# vca.net
KiCad netlist of a schematic drawn in Altium Designer
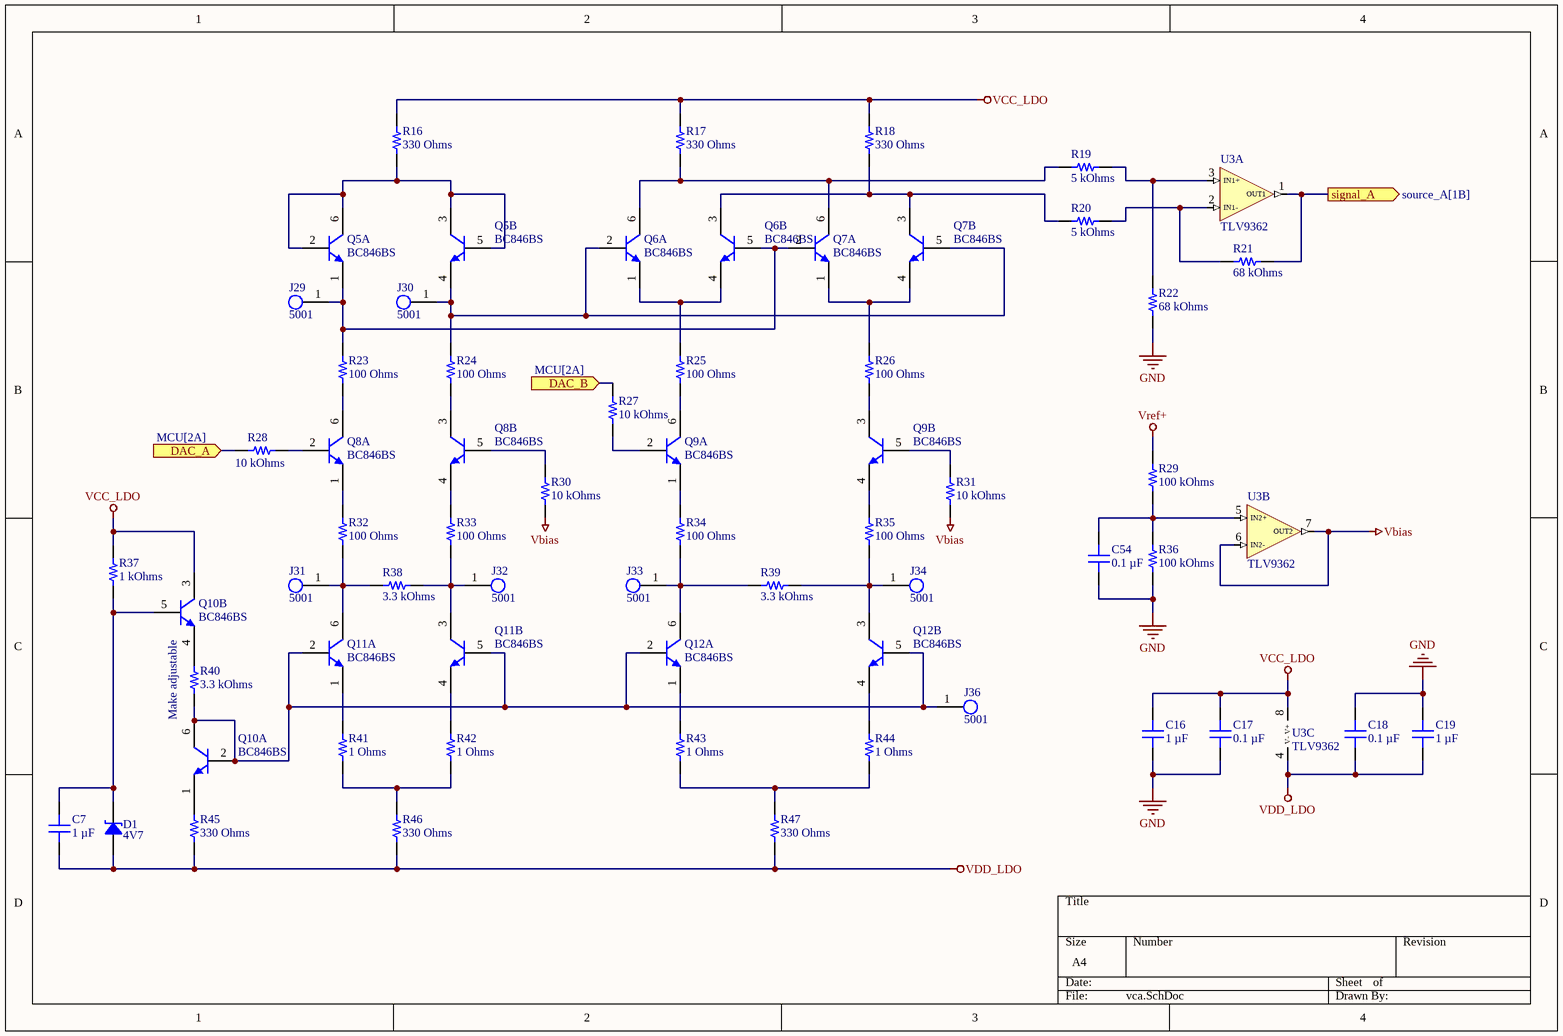
[diagram p0: vca.SchDoc]

(export (version "E")
  (design (tool "Eeschema 10.0.6"))
  (components
    (comp (ref "C7")
      (value "1 µF")
      (footprint "CAP 1206_3216 - 0.8MM")
      (description "CAP CER 1UF 50V X7R 1206")
      (fields
        (field (name "PART NUMBER") "885012208093")
        (field (name "CAPACITANCE") "1 µF")
        (field (name "MANUFACTURER") "Würth Elektronik")
      )
      (libsource (lib "Celestial Altium Library - altium_library") (part "Capacitor"))
    )
    (comp (ref "C16")
      (value "1 µF")
      (footprint "CAP 1206_3216 - 0.8MM")
      (description "CAP CER 1UF 50V X7R 1206")
      (fields
        (field (name "PART NUMBER") "885012208093")
        (field (name "CAPACITANCE") "1 µF")
        (field (name "MANUFACTURER") "Würth Elektronik")
      )
      (libsource (lib "Celestial Altium Library - altium_library") (part "Capacitor"))
    )
    (comp (ref "C17")
      (value "0.1 µF")
      (footprint "CAP 1206_3216 - 0.8MM")
      (description "CAP CER 0.1UF 50V X7R 1206")
      (fields
        (field (name "PART NUMBER") "885012208087")
        (field (name "CAPACITANCE") "0.1 µF")
        (field (name "MANUFACTURER") "Würth Elektronik")
      )
      (libsource (lib "Celestial Altium Library - altium_library") (part "Capacitor"))
    )
    (comp (ref "C18")
      (value "0.1 µF")
      (footprint "CAP 1206_3216 - 0.8MM")
      (description "CAP CER 0.1UF 50V X7R 1206")
      (fields
        (field (name "PART NUMBER") "885012208087")
        (field (name "CAPACITANCE") "0.1 µF")
        (field (name "MANUFACTURER") "Würth Elektronik")
      )
      (libsource (lib "Celestial Altium Library - altium_library") (part "Capacitor"))
    )
    (comp (ref "C19")
      (value "1 µF")
      (footprint "CAP 1206_3216 - 0.8MM")
      (description "CAP CER 1UF 50V X7R 1206")
      (fields
        (field (name "PART NUMBER") "885012208093")
        (field (name "CAPACITANCE") "1 µF")
        (field (name "MANUFACTURER") "Würth Elektronik")
      )
      (libsource (lib "Celestial Altium Library - altium_library") (part "Capacitor"))
    )
    (comp (ref "C54")
      (value "0.1 µF")
      (footprint "CAP 1206_3216 - 0.8MM")
      (description "CAP CER 0.1UF 50V X7R 1206")
      (fields
        (field (name "PART NUMBER") "885012208087")
        (field (name "CAPACITANCE") "0.1 µF")
        (field (name "MANUFACTURER") "Würth Elektronik")
      )
      (libsource (lib "Celestial Altium Library - altium_library") (part "Capacitor"))
    )
    (comp (ref "D1") (value "4V7") (footprint "SOD323") (libsource (lib "za_koncar") (part "BZX38450-C4V7X")))
    (comp (ref "J29")
      (value "5001")
      (footprint "FP-5001-MFG")
      (description "PC TEST POINT MINIATURE BLACK")
      (libsource (lib "za_koncar") (part "CMP-2000-05181-2"))
    )
    (comp (ref "J30")
      (value "5001")
      (footprint "FP-5001-MFG")
      (description "PC TEST POINT MINIATURE BLACK")
      (libsource (lib "za_koncar") (part "CMP-2000-05181-2"))
    )
    (comp (ref "J31")
      (value "5001")
      (footprint "FP-5001-MFG")
      (description "PC TEST POINT MINIATURE BLACK")
      (libsource (lib "za_koncar") (part "CMP-2000-05181-2"))
    )
    (comp (ref "J32")
      (value "5001")
      (footprint "FP-5001-MFG")
      (description "PC TEST POINT MINIATURE BLACK")
      (libsource (lib "za_koncar") (part "CMP-2000-05181-2"))
    )
    (comp (ref "J33")
      (value "5001")
      (footprint "FP-5001-MFG")
      (description "PC TEST POINT MINIATURE BLACK")
      (libsource (lib "za_koncar") (part "CMP-2000-05181-2"))
    )
    (comp (ref "J34")
      (value "5001")
      (footprint "FP-5001-MFG")
      (description "PC TEST POINT MINIATURE BLACK")
      (libsource (lib "za_koncar") (part "CMP-2000-05181-2"))
    )
    (comp (ref "J36")
      (value "5001")
      (footprint "FP-5001-MFG")
      (description "PC TEST POINT MINIATURE BLACK")
      (libsource (lib "za_koncar") (part "CMP-2000-05181-2"))
    )
    (comp (ref "Q5")
      (value "BC846BS")
      (footprint "TSOP65P210X110-6N")
      (description "65 V, 100 mA matched NPN/NPN general-purpose transistor")
      (libsource (lib "za_koncar") (part "BC846BS"))
    )
    (comp (ref "Q6")
      (value "BC846BS")
      (footprint "TSOP65P210X110-6N")
      (description "65 V, 100 mA matched NPN/NPN general-purpose transistor")
      (libsource (lib "za_koncar") (part "BC846BS"))
    )
    (comp (ref "Q7")
      (value "BC846BS")
      (footprint "TSOP65P210X110-6N")
      (description "65 V, 100 mA matched NPN/NPN general-purpose transistor")
      (libsource (lib "za_koncar") (part "BC846BS"))
    )
    (comp (ref "Q8")
      (value "BC846BS")
      (footprint "TSOP65P210X110-6N")
      (description "65 V, 100 mA matched NPN/NPN general-purpose transistor")
      (libsource (lib "za_koncar") (part "BC846BS"))
    )
    (comp (ref "Q9")
      (value "BC846BS")
      (footprint "TSOP65P210X110-6N")
      (description "65 V, 100 mA matched NPN/NPN general-purpose transistor")
      (libsource (lib "za_koncar") (part "BC846BS"))
    )
    (comp (ref "Q10")
      (value "BC846BS")
      (footprint "TSOP65P210X110-6N")
      (description "65 V, 100 mA matched NPN/NPN general-purpose transistor")
      (libsource (lib "za_koncar") (part "BC846BS"))
    )
    (comp (ref "Q11")
      (value "BC846BS")
      (footprint "TSOP65P210X110-6N")
      (description "65 V, 100 mA matched NPN/NPN general-purpose transistor")
      (libsource (lib "za_koncar") (part "BC846BS"))
    )
    (comp (ref "Q12")
      (value "BC846BS")
      (footprint "TSOP65P210X110-6N")
      (description "65 V, 100 mA matched NPN/NPN general-purpose transistor")
      (libsource (lib "za_koncar") (part "BC846BS"))
    )
    (comp (ref "R16")
      (value "330 Ohms")
      (footprint "YAGEO RES 1206_3216")
      (description "RES SMD 330 OHM 1% 1/4W 1206")
      (fields (field (name "PART NUMBER") "RT1206FRD07330RL") (field (name "MANUFACTURER") "Yageo"))
      (libsource (lib "Celestial Altium Library - altium_library") (part "Resistor"))
    )
    (comp (ref "R17")
      (value "330 Ohms")
      (footprint "YAGEO RES 1206_3216")
      (description "RES SMD 330 OHM 1% 1/4W 1206")
      (fields (field (name "PART NUMBER") "RT1206FRD07330RL") (field (name "MANUFACTURER") "Yageo"))
      (libsource (lib "Celestial Altium Library - altium_library") (part "Resistor"))
    )
    (comp (ref "R18")
      (value "330 Ohms")
      (footprint "YAGEO RES 1206_3216")
      (description "RES SMD 330 OHM 1% 1/4W 1206")
      (fields (field (name "PART NUMBER") "RT1206FRD07330RL") (field (name "MANUFACTURER") "Yageo"))
      (libsource (lib "Celestial Altium Library - altium_library") (part "Resistor"))
    )
    (comp (ref "R19")
      (value "5 kOhms")
      (footprint "YAGEO RES 1206_3216")
      (description "RES 5K OHM 1% 1/4W 1206")
      (fields (field (name "PART NUMBER") "RT1206FRE075KL") (field (name "MANUFACTURER") "Yageo"))
      (libsource (lib "Celestial Altium Library - altium_library") (part "Resistor"))
    )
    (comp (ref "R20")
      (value "5 kOhms")
      (footprint "YAGEO RES 1206_3216")
      (description "RES 5K OHM 1% 1/4W 1206")
      (fields (field (name "PART NUMBER") "RT1206FRE075KL") (field (name "MANUFACTURER") "Yageo"))
      (libsource (lib "Celestial Altium Library - altium_library") (part "Resistor"))
    )
    (comp (ref "R21")
      (value "68 kOhms")
      (footprint "YAGEO RES 1206_3216")
      (description "RES SMD 68K OHM 1% 1/4W 1206")
      (fields (field (name "PART NUMBER") "RT1206FRE0768KL") (field (name "MANUFACTURER") "Yageo"))
      (libsource (lib "Celestial Altium Library - altium_library") (part "Resistor"))
    )
    (comp (ref "R22")
      (value "68 kOhms")
      (footprint "YAGEO RES 1206_3216")
      (description "RES SMD 68K OHM 1% 1/4W 1206")
      (fields (field (name "PART NUMBER") "RT1206FRE0768KL") (field (name "MANUFACTURER") "Yageo"))
      (libsource (lib "Celestial Altium Library - altium_library") (part "Resistor"))
    )
    (comp (ref "R23")
      (value "100 Ohms")
      (footprint "YAGEO RES 1206_3216")
      (description "RES SMD 100 OHM 1% 1/4W 1206")
      (fields (field (name "PART NUMBER") "RT1206FRD07100RL") (field (name "MANUFACTURER") "Yageo"))
      (libsource (lib "Celestial Altium Library - altium_library") (part "Resistor"))
    )
    (comp (ref "R24")
      (value "100 Ohms")
      (footprint "YAGEO RES 1206_3216")
      (description "RES SMD 100 OHM 1% 1/4W 1206")
      (fields (field (name "PART NUMBER") "RT1206FRD07100RL") (field (name "MANUFACTURER") "Yageo"))
      (libsource (lib "Celestial Altium Library - altium_library") (part "Resistor"))
    )
    (comp (ref "R25")
      (value "100 Ohms")
      (footprint "YAGEO RES 1206_3216")
      (description "RES SMD 100 OHM 1% 1/4W 1206")
      (fields (field (name "PART NUMBER") "RT1206FRD07100RL") (field (name "MANUFACTURER") "Yageo"))
      (libsource (lib "Celestial Altium Library - altium_library") (part "Resistor"))
    )
    (comp (ref "R26")
      (value "100 Ohms")
      (footprint "YAGEO RES 1206_3216")
      (description "RES SMD 100 OHM 1% 1/4W 1206")
      (fields (field (name "PART NUMBER") "RT1206FRD07100RL") (field (name "MANUFACTURER") "Yageo"))
      (libsource (lib "Celestial Altium Library - altium_library") (part "Resistor"))
    )
    (comp (ref "R27")
      (value "10 kOhms")
      (footprint "YAGEO RES 1206_3216")
      (description "RES SMD 10K OHM 1% 1/4W 1206")
      (fields (field (name "PART NUMBER") "RT1206FRE0710KL") (field (name "MANUFACTURER") "Yageo"))
      (libsource (lib "Celestial Altium Library - altium_library") (part "Resistor"))
    )
    (comp (ref "R28")
      (value "10 kOhms")
      (footprint "YAGEO RES 1206_3216")
      (description "RES SMD 10K OHM 1% 1/4W 1206")
      (fields (field (name "PART NUMBER") "RT1206FRE0710KL") (field (name "MANUFACTURER") "Yageo"))
      (libsource (lib "Celestial Altium Library - altium_library") (part "Resistor"))
    )
    (comp (ref "R29")
      (value "100 kOhms")
      (footprint "YAGEO RES 1206_3216")
      (description "RES SMD 100K OHM 1% 1/4W 1206")
      (fields (field (name "PART NUMBER") "RT1206FRE07100KL") (field (name "MANUFACTURER") "Yageo"))
      (libsource (lib "Celestial Altium Library - altium_library") (part "Resistor"))
    )
    (comp (ref "R30")
      (value "10 kOhms")
      (footprint "YAGEO RES 1206_3216")
      (description "RES SMD 10K OHM 1% 1/4W 1206")
      (fields (field (name "PART NUMBER") "RT1206FRE0710KL") (field (name "MANUFACTURER") "Yageo"))
      (libsource (lib "Celestial Altium Library - altium_library") (part "Resistor"))
    )
    (comp (ref "R31")
      (value "10 kOhms")
      (footprint "YAGEO RES 1206_3216")
      (description "RES SMD 10K OHM 1% 1/4W 1206")
      (fields (field (name "PART NUMBER") "RT1206FRE0710KL") (field (name "MANUFACTURER") "Yageo"))
      (libsource (lib "Celestial Altium Library - altium_library") (part "Resistor"))
    )
    (comp (ref "R32")
      (value "100 Ohms")
      (footprint "YAGEO RES 1206_3216")
      (description "RES SMD 100 OHM 1% 1/4W 1206")
      (fields (field (name "PART NUMBER") "RT1206FRD07100RL") (field (name "MANUFACTURER") "Yageo"))
      (libsource (lib "Celestial Altium Library - altium_library") (part "Resistor"))
    )
    (comp (ref "R33")
      (value "100 Ohms")
      (footprint "YAGEO RES 1206_3216")
      (description "RES SMD 100 OHM 1% 1/4W 1206")
      (fields (field (name "PART NUMBER") "RT1206FRD07100RL") (field (name "MANUFACTURER") "Yageo"))
      (libsource (lib "Celestial Altium Library - altium_library") (part "Resistor"))
    )
    (comp (ref "R34")
      (value "100 Ohms")
      (footprint "YAGEO RES 1206_3216")
      (description "RES SMD 100 OHM 1% 1/4W 1206")
      (fields (field (name "PART NUMBER") "RT1206FRD07100RL") (field (name "MANUFACTURER") "Yageo"))
      (libsource (lib "Celestial Altium Library - altium_library") (part "Resistor"))
    )
    (comp (ref "R35")
      (value "100 Ohms")
      (footprint "YAGEO RES 1206_3216")
      (description "RES SMD 100 OHM 1% 1/4W 1206")
      (fields (field (name "PART NUMBER") "RT1206FRD07100RL") (field (name "MANUFACTURER") "Yageo"))
      (libsource (lib "Celestial Altium Library - altium_library") (part "Resistor"))
    )
    (comp (ref "R36")
      (value "100 kOhms")
      (footprint "YAGEO RES 1206_3216")
      (description "RES SMD 100K OHM 1% 1/4W 1206")
      (fields (field (name "PART NUMBER") "RT1206FRE07100KL") (field (name "MANUFACTURER") "Yageo"))
      (libsource (lib "Celestial Altium Library - altium_library") (part "Resistor"))
    )
    (comp (ref "R37")
      (value "1 kOhms")
      (footprint "YAGEO RES 1206_3216")
      (description "RES SMD 1K OHM 1% 1/4W 1206")
      (fields (field (name "PART NUMBER") "RT1206FRE071KL") (field (name "MANUFACTURER") "Yageo"))
      (libsource (lib "Celestial Altium Library - altium_library") (part "Resistor"))
    )
    (comp (ref "R38")
      (value "3.3 kOhms")
      (footprint "YAGEO RES 1206_3216")
      (description "RES SMD 3.3K OHM 1% 1/4W 1206")
      (fields (field (name "PART NUMBER") "RT1206FRE073K3L") (field (name "MANUFACTURER") "Yageo"))
      (libsource (lib "Celestial Altium Library - altium_library") (part "Resistor"))
    )
    (comp (ref "R39")
      (value "3.3 kOhms")
      (footprint "YAGEO RES 1206_3216")
      (description "RES SMD 3.3K OHM 1% 1/4W 1206")
      (fields (field (name "PART NUMBER") "RT1206FRE073K3L") (field (name "MANUFACTURER") "Yageo"))
      (libsource (lib "Celestial Altium Library - altium_library") (part "Resistor"))
    )
    (comp (ref "R40")
      (value "3.3 kOhms")
      (footprint "YAGEO RES 1206_3216")
      (description "RES SMD 3.3K OHM 1% 1/4W 1206")
      (fields (field (name "PART NUMBER") "RT1206FRE073K3L") (field (name "MANUFACTURER") "Yageo"))
      (libsource (lib "Celestial Altium Library - altium_library") (part "Resistor"))
    )
    (comp (ref "R41")
      (value "1 Ohms")
      (footprint "YAGEO RES 1206_3216")
      (description "RES 1 OHM 0.1% 1/4W 1206")
      (fields (field (name "PART NUMBER") "RT1206BRD071RL") (field (name "MANUFACTURER") "Yageo"))
      (libsource (lib "Celestial Altium Library - altium_library") (part "Resistor"))
    )
    (comp (ref "R42")
      (value "1 Ohms")
      (footprint "YAGEO RES 1206_3216")
      (description "RES 1 OHM 0.1% 1/4W 1206")
      (fields (field (name "PART NUMBER") "RT1206BRD071RL") (field (name "MANUFACTURER") "Yageo"))
      (libsource (lib "Celestial Altium Library - altium_library") (part "Resistor"))
    )
    (comp (ref "R43")
      (value "1 Ohms")
      (footprint "YAGEO RES 1206_3216")
      (description "RES 1 OHM 0.1% 1/4W 1206")
      (fields (field (name "PART NUMBER") "RT1206BRD071RL") (field (name "MANUFACTURER") "Yageo"))
      (libsource (lib "Celestial Altium Library - altium_library") (part "Resistor"))
    )
    (comp (ref "R44")
      (value "1 Ohms")
      (footprint "YAGEO RES 1206_3216")
      (description "RES 1 OHM 0.1% 1/4W 1206")
      (fields (field (name "PART NUMBER") "RT1206BRD071RL") (field (name "MANUFACTURER") "Yageo"))
      (libsource (lib "Celestial Altium Library - altium_library") (part "Resistor"))
    )
    (comp (ref "R45")
      (value "330 Ohms")
      (footprint "YAGEO RES 1206_3216")
      (description "RES SMD 330 OHM 1% 1/4W 1206")
      (fields (field (name "PART NUMBER") "RT1206FRD07330RL") (field (name "MANUFACTURER") "Yageo"))
      (libsource (lib "Celestial Altium Library - altium_library") (part "Resistor"))
    )
    (comp (ref "R46")
      (value "330 Ohms")
      (footprint "YAGEO RES 1206_3216")
      (description "RES SMD 330 OHM 1% 1/4W 1206")
      (fields (field (name "PART NUMBER") "RT1206FRD07330RL") (field (name "MANUFACTURER") "Yageo"))
      (libsource (lib "Celestial Altium Library - altium_library") (part "Resistor"))
    )
    (comp (ref "R47")
      (value "330 Ohms")
      (footprint "YAGEO RES 1206_3216")
      (description "RES SMD 330 OHM 1% 1/4W 1206")
      (fields (field (name "PART NUMBER") "RT1206FRD07330RL") (field (name "MANUFACTURER") "Yageo"))
      (libsource (lib "Celestial Altium Library - altium_library") (part "Resistor"))
    )
    (comp (ref "U3")
      (value "TLV9362")
      (footprint "za_koncar:SOIC8-127P600X175-8N")
      (description "TLV936x 10-MHz, 40-V, RRO, Operational Amplifie")
      (libsource (lib "za_koncar") (part "TLV9362"))
    )
  )
  (nets
    (net (code "1") (name "/DAC_A") (class "Default")
      (node (ref "R28") (pin "1") (pinfunction "1_1") (pintype "passive"))
    )
    (net (code "2") (name "/DAC_B") (class "Default")
      (node (ref "R27") (pin "1") (pinfunction "1_1") (pintype "passive"))
    )
    (net (code "3") (name "/signal_A") (class "Default")
      (node (ref "R21") (pin "1") (pinfunction "1_1") (pintype "passive"))
      (node (ref "U3") (pin "1") (pinfunction "OUT1_1") (pintype "output"))
    )
    (net (code "4") (name "GND") (class "Default")
      (node (ref "C16") (pin "1") (pinfunction "1_1") (pintype "passive"))
      (node (ref "C17") (pin "1") (pinfunction "1_1") (pintype "passive"))
      (node (ref "C18") (pin "2") (pinfunction "2_2") (pintype "passive"))
      (node (ref "C19") (pin "2") (pinfunction "2_2") (pintype "passive"))
      (node (ref "C54") (pin "1") (pinfunction "1_1") (pintype "passive"))
      (node (ref "R22") (pin "2") (pinfunction "2_2") (pintype "passive"))
      (node (ref "R36") (pin "1") (pinfunction "1_1") (pintype "passive"))
    )
    (net (code "5") (name "Net-(Q5A-B1)") (class "Default")
      (node (ref "Q5") (pin "2") (pinfunction "B1_2") (pintype "passive"))
      (node (ref "Q5") (pin "3") (pinfunction "C2_3") (pintype "passive"))
      (node (ref "Q5") (pin "5") (pinfunction "B2_5") (pintype "passive"))
      (node (ref "Q5") (pin "6") (pinfunction "C1_6") (pintype "passive"))
      (node (ref "R16") (pin "1") (pinfunction "1_1") (pintype "passive"))
    )
    (net (code "6") (name "Net-(Q5A-E1)") (class "Default")
      (node (ref "J29") (pin "1") (pinfunction "1_1") (pintype "passive"))
      (node (ref "Q5") (pin "1") (pinfunction "E1_1") (pintype "passive"))
      (node (ref "Q6") (pin "5") (pinfunction "B2_5") (pintype "passive"))
      (node (ref "Q7") (pin "2") (pinfunction "B1_2") (pintype "passive"))
      (node (ref "R23") (pin "2") (pinfunction "2_2") (pintype "passive"))
    )
    (net (code "7") (name "Net-(Q5B-E2)") (class "Default")
      (node (ref "J30") (pin "1") (pinfunction "1_1") (pintype "passive"))
      (node (ref "Q5") (pin "4") (pinfunction "E2_4") (pintype "passive"))
      (node (ref "Q6") (pin "2") (pinfunction "B1_2") (pintype "passive"))
      (node (ref "Q7") (pin "5") (pinfunction "B2_5") (pintype "passive"))
      (node (ref "R24") (pin "2") (pinfunction "2_2") (pintype "passive"))
    )
    (net (code "8") (name "Net-(Q6A-C1)") (class "Default")
      (node (ref "Q6") (pin "6") (pinfunction "C1_6") (pintype "passive"))
      (node (ref "Q7") (pin "6") (pinfunction "C1_6") (pintype "passive"))
      (node (ref "R17") (pin "1") (pinfunction "1_1") (pintype "passive"))
      (node (ref "R19") (pin "2") (pinfunction "2_2") (pintype "passive"))
    )
    (net (code "9") (name "Net-(Q6A-E1)") (class "Default")
      (node (ref "Q6") (pin "1") (pinfunction "E1_1") (pintype "passive"))
      (node (ref "Q6") (pin "4") (pinfunction "E2_4") (pintype "passive"))
      (node (ref "R25") (pin "2") (pinfunction "2_2") (pintype "passive"))
    )
    (net (code "10") (name "Net-(Q6B-C2)") (class "Default")
      (node (ref "Q6") (pin "3") (pinfunction "C2_3") (pintype "passive"))
      (node (ref "Q7") (pin "3") (pinfunction "C2_3") (pintype "passive"))
      (node (ref "R18") (pin "1") (pinfunction "1_1") (pintype "passive"))
      (node (ref "R20") (pin "2") (pinfunction "2_2") (pintype "passive"))
    )
    (net (code "11") (name "Net-(Q7A-E1)") (class "Default")
      (node (ref "Q7") (pin "1") (pinfunction "E1_1") (pintype "passive"))
      (node (ref "Q7") (pin "4") (pinfunction "E2_4") (pintype "passive"))
      (node (ref "R26") (pin "2") (pinfunction "2_2") (pintype "passive"))
    )
    (net (code "12") (name "Net-(Q8A-B1)") (class "Default")
      (node (ref "Q8") (pin "2") (pinfunction "B1_2") (pintype "passive"))
      (node (ref "R28") (pin "2") (pinfunction "2_2") (pintype "passive"))
    )
    (net (code "13") (name "Net-(Q8A-C1)") (class "Default")
      (node (ref "Q8") (pin "6") (pinfunction "C1_6") (pintype "passive"))
      (node (ref "R23") (pin "1") (pinfunction "1_1") (pintype "passive"))
    )
    (net (code "14") (name "Net-(Q8A-E1)") (class "Default")
      (node (ref "Q8") (pin "1") (pinfunction "E1_1") (pintype "passive"))
      (node (ref "R32") (pin "2") (pinfunction "2_2") (pintype "passive"))
    )
    (net (code "15") (name "Net-(Q8B-B2)") (class "Default")
      (node (ref "Q8") (pin "5") (pinfunction "B2_5") (pintype "passive"))
      (node (ref "R30") (pin "2") (pinfunction "2_2") (pintype "passive"))
    )
    (net (code "16") (name "Net-(Q8B-C2)") (class "Default")
      (node (ref "Q8") (pin "3") (pinfunction "C2_3") (pintype "passive"))
      (node (ref "R24") (pin "1") (pinfunction "1_1") (pintype "passive"))
    )
    (net (code "17") (name "Net-(Q8B-E2)") (class "Default")
      (node (ref "Q8") (pin "4") (pinfunction "E2_4") (pintype "passive"))
      (node (ref "R33") (pin "2") (pinfunction "2_2") (pintype "passive"))
    )
    (net (code "18") (name "Net-(Q9A-B1)") (class "Default")
      (node (ref "Q9") (pin "2") (pinfunction "B1_2") (pintype "passive"))
      (node (ref "R27") (pin "2") (pinfunction "2_2") (pintype "passive"))
    )
    (net (code "19") (name "Net-(Q9A-C1)") (class "Default")
      (node (ref "Q9") (pin "6") (pinfunction "C1_6") (pintype "passive"))
      (node (ref "R25") (pin "1") (pinfunction "1_1") (pintype "passive"))
    )
    (net (code "20") (name "Net-(Q9A-E1)") (class "Default")
      (node (ref "Q9") (pin "1") (pinfunction "E1_1") (pintype "passive"))
      (node (ref "R34") (pin "2") (pinfunction "2_2") (pintype "passive"))
    )
    (net (code "21") (name "Net-(Q9B-B2)") (class "Default")
      (node (ref "Q9") (pin "5") (pinfunction "B2_5") (pintype "passive"))
      (node (ref "R31") (pin "2") (pinfunction "2_2") (pintype "passive"))
    )
    (net (code "22") (name "Net-(Q9B-C2)") (class "Default")
      (node (ref "Q9") (pin "3") (pinfunction "C2_3") (pintype "passive"))
      (node (ref "R26") (pin "1") (pinfunction "1_1") (pintype "passive"))
    )
    (net (code "23") (name "Net-(Q9B-E2)") (class "Default")
      (node (ref "Q9") (pin "4") (pinfunction "E2_4") (pintype "passive"))
      (node (ref "R35") (pin "2") (pinfunction "2_2") (pintype "passive"))
    )
    (net (code "24") (name "Net-(Q10A-B1)") (class "Default")
      (node (ref "J36") (pin "1") (pinfunction "1_1") (pintype "passive"))
      (node (ref "Q10") (pin "2") (pinfunction "B1_2") (pintype "passive"))
      (node (ref "Q10") (pin "6") (pinfunction "C1_6") (pintype "passive"))
      (node (ref "Q11") (pin "2") (pinfunction "B1_2") (pintype "passive"))
      (node (ref "Q11") (pin "5") (pinfunction "B2_5") (pintype "passive"))
      (node (ref "Q12") (pin "2") (pinfunction "B1_2") (pintype "passive"))
      (node (ref "Q12") (pin "5") (pinfunction "B2_5") (pintype "passive"))
      (node (ref "R40") (pin "2") (pinfunction "2_2") (pintype "passive"))
    )
    (net (code "25") (name "Net-(Q10A-E1)") (class "Default")
      (node (ref "Q10") (pin "1") (pinfunction "E1_1") (pintype "passive"))
      (node (ref "R45") (pin "2") (pinfunction "2_2") (pintype "passive"))
    )
    (net (code "26") (name "Net-(Q10B-B2)") (class "Default")
      (node (ref "C7") (pin "2") (pinfunction "2_2") (pintype "passive"))
      (node (ref "D1") (pin "2") (pinfunction "2_2") (pintype "passive"))
      (node (ref "Q10") (pin "5") (pinfunction "B2_5") (pintype "passive"))
      (node (ref "R37") (pin "1") (pinfunction "1_1") (pintype "passive"))
    )
    (net (code "27") (name "Net-(Q10B-E2)") (class "Default")
      (node (ref "Q10") (pin "4") (pinfunction "E2_4") (pintype "passive"))
      (node (ref "R40") (pin "1") (pinfunction "1_1") (pintype "passive"))
    )
    (net (code "28") (name "Net-(Q11A-C1)") (class "Default")
      (node (ref "J31") (pin "1") (pinfunction "1_1") (pintype "passive"))
      (node (ref "Q11") (pin "6") (pinfunction "C1_6") (pintype "passive"))
      (node (ref "R32") (pin "1") (pinfunction "1_1") (pintype "passive"))
      (node (ref "R38") (pin "2") (pinfunction "2_2") (pintype "passive"))
    )
    (net (code "29") (name "Net-(Q11A-E1)") (class "Default")
      (node (ref "Q11") (pin "1") (pinfunction "E1_1") (pintype "passive"))
      (node (ref "R41") (pin "2") (pinfunction "2_2") (pintype "passive"))
    )
    (net (code "30") (name "Net-(Q11B-C2)") (class "Default")
      (node (ref "J32") (pin "1") (pinfunction "1_1") (pintype "passive"))
      (node (ref "Q11") (pin "3") (pinfunction "C2_3") (pintype "passive"))
      (node (ref "R33") (pin "1") (pinfunction "1_1") (pintype "passive"))
      (node (ref "R38") (pin "1") (pinfunction "1_1") (pintype "passive"))
    )
    (net (code "31") (name "Net-(Q11B-E2)") (class "Default")
      (node (ref "Q11") (pin "4") (pinfunction "E2_4") (pintype "passive"))
      (node (ref "R42") (pin "2") (pinfunction "2_2") (pintype "passive"))
    )
    (net (code "32") (name "Net-(Q12A-C1)") (class "Default")
      (node (ref "J33") (pin "1") (pinfunction "1_1") (pintype "passive"))
      (node (ref "Q12") (pin "6") (pinfunction "C1_6") (pintype "passive"))
      (node (ref "R34") (pin "1") (pinfunction "1_1") (pintype "passive"))
      (node (ref "R39") (pin "2") (pinfunction "2_2") (pintype "passive"))
    )
    (net (code "33") (name "Net-(Q12A-E1)") (class "Default")
      (node (ref "Q12") (pin "1") (pinfunction "E1_1") (pintype "passive"))
      (node (ref "R43") (pin "2") (pinfunction "2_2") (pintype "passive"))
    )
    (net (code "34") (name "Net-(Q12B-C2)") (class "Default")
      (node (ref "J34") (pin "1") (pinfunction "1_1") (pintype "passive"))
      (node (ref "Q12") (pin "3") (pinfunction "C2_3") (pintype "passive"))
      (node (ref "R35") (pin "1") (pinfunction "1_1") (pintype "passive"))
      (node (ref "R39") (pin "1") (pinfunction "1_1") (pintype "passive"))
    )
    (net (code "35") (name "Net-(Q12B-E2)") (class "Default")
      (node (ref "Q12") (pin "4") (pinfunction "E2_4") (pintype "passive"))
      (node (ref "R44") (pin "2") (pinfunction "2_2") (pintype "passive"))
    )
    (net (code "36") (name "Net-(R41-Pad1)") (class "Default")
      (node (ref "R41") (pin "1") (pinfunction "1_1") (pintype "passive"))
      (node (ref "R42") (pin "1") (pinfunction "1_1") (pintype "passive"))
      (node (ref "R46") (pin "2") (pinfunction "2_2") (pintype "passive"))
    )
    (net (code "37") (name "Net-(R43-Pad1)") (class "Default")
      (node (ref "R43") (pin "1") (pinfunction "1_1") (pintype "passive"))
      (node (ref "R44") (pin "1") (pinfunction "1_1") (pintype "passive"))
      (node (ref "R47") (pin "2") (pinfunction "2_2") (pintype "passive"))
    )
    (net (code "38") (name "Net-(U3A-IN1+)") (class "Default")
      (node (ref "R19") (pin "1") (pinfunction "1_1") (pintype "passive"))
      (node (ref "R22") (pin "1") (pinfunction "1_1") (pintype "passive"))
      (node (ref "U3") (pin "3") (pinfunction "IN1+_3") (pintype "input"))
    )
    (net (code "39") (name "Net-(U3A-IN1-)") (class "Default")
      (node (ref "R20") (pin "1") (pinfunction "1_1") (pintype "passive"))
      (node (ref "R21") (pin "2") (pinfunction "2_2") (pintype "passive"))
      (node (ref "U3") (pin "2") (pinfunction "IN1-_2") (pintype "input"))
    )
    (net (code "40") (name "Net-(U3B-IN2+)") (class "Default")
      (node (ref "C54") (pin "2") (pinfunction "2_2") (pintype "passive"))
      (node (ref "R29") (pin "1") (pinfunction "1_1") (pintype "passive"))
      (node (ref "R36") (pin "2") (pinfunction "2_2") (pintype "passive"))
      (node (ref "U3") (pin "5") (pinfunction "IN2+_5") (pintype "input"))
    )
    (net (code "41") (name "VCC_LDO") (class "Default")
      (node (ref "C16") (pin "2") (pinfunction "2_2") (pintype "passive"))
      (node (ref "C17") (pin "2") (pinfunction "2_2") (pintype "passive"))
      (node (ref "Q10") (pin "3") (pinfunction "C2_3") (pintype "passive"))
      (node (ref "R16") (pin "2") (pinfunction "2_2") (pintype "passive"))
      (node (ref "R17") (pin "2") (pinfunction "2_2") (pintype "passive"))
      (node (ref "R18") (pin "2") (pinfunction "2_2") (pintype "passive"))
      (node (ref "R37") (pin "2") (pinfunction "2_2") (pintype "passive"))
      (node (ref "U3") (pin "8") (pinfunction "V+_8") (pintype "power_in"))
    )
    (net (code "42") (name "VDD_LDO") (class "Default")
      (node (ref "C18") (pin "1") (pinfunction "1_1") (pintype "passive"))
      (node (ref "C19") (pin "1") (pinfunction "1_1") (pintype "passive"))
      (node (ref "C7") (pin "1") (pinfunction "1_1") (pintype "passive"))
      (node (ref "D1") (pin "1") (pinfunction "1_1") (pintype "passive"))
      (node (ref "R45") (pin "1") (pinfunction "1_1") (pintype "passive"))
      (node (ref "R46") (pin "1") (pinfunction "1_1") (pintype "passive"))
      (node (ref "R47") (pin "1") (pinfunction "1_1") (pintype "passive"))
      (node (ref "U3") (pin "4") (pinfunction "V-_4") (pintype "power_in"))
    )
    (net (code "43") (name "Vbias") (class "Default")
      (node (ref "R30") (pin "1") (pinfunction "1_1") (pintype "passive"))
      (node (ref "R31") (pin "1") (pinfunction "1_1") (pintype "passive"))
      (node (ref "U3") (pin "6") (pinfunction "IN2-_6") (pintype "input"))
      (node (ref "U3") (pin "7") (pinfunction "OUT2_7") (pintype "output"))
    )
    (net (code "44") (name "Vref+") (class "Default")
      (node (ref "R29") (pin "2") (pinfunction "2_2") (pintype "passive"))
    )
  )
)
